# BSPD_RevE.net
KiCad netlist of a schematic drawn in EAGLE
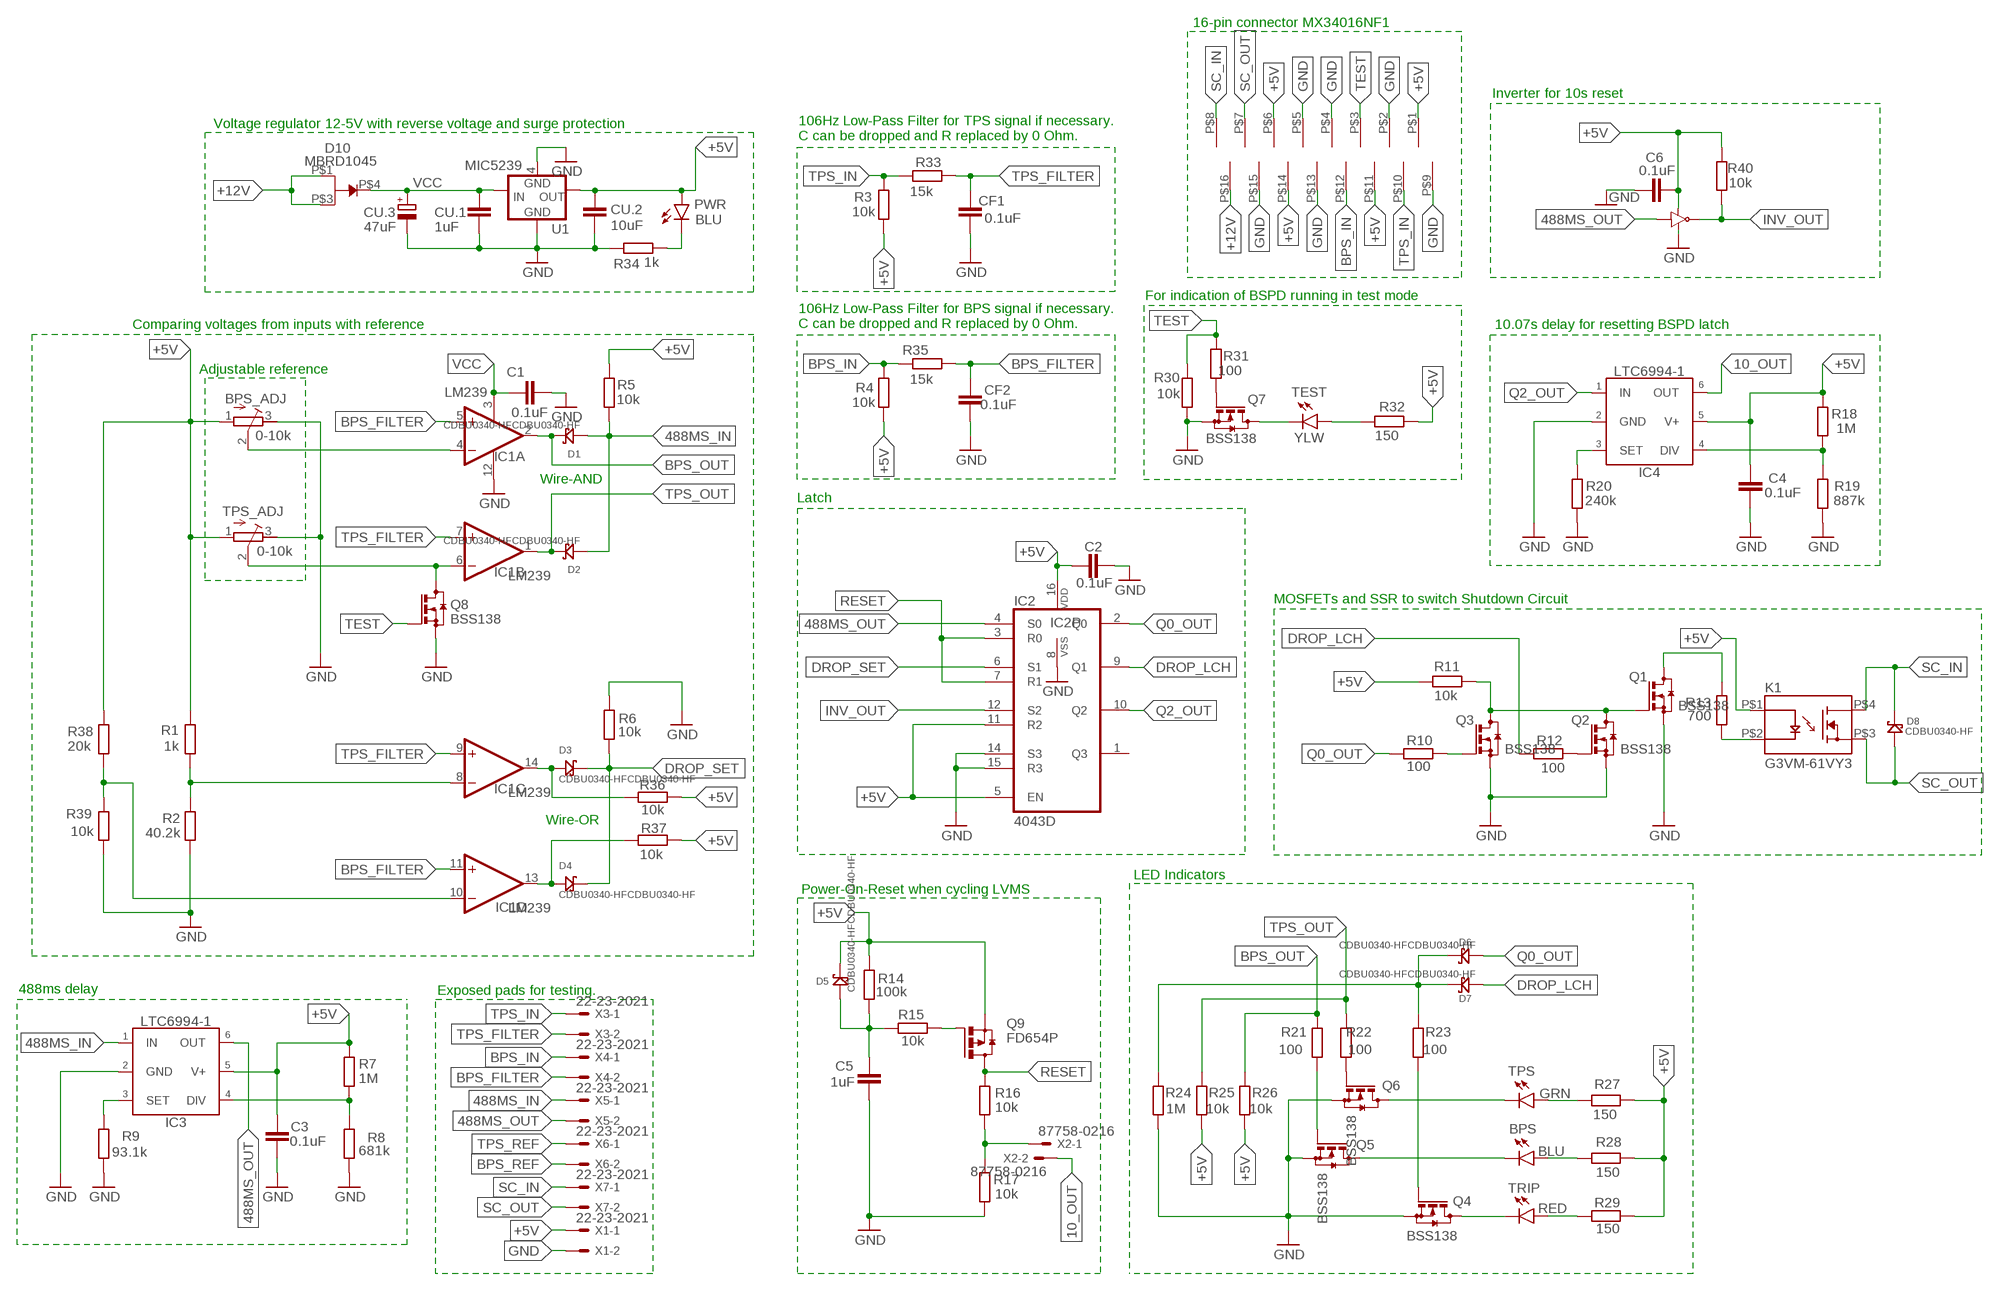
[diagram p0: schematic, sheet 1]

(export (version "E")
  (design (tool "Eeschema 10.0.6"))
  (components
    (comp (ref "BPS")
      (value "BLU")
      (footprint "eagle-import:SML1206")
      (libsource (lib "eagle-import") (part "LEDSML1206"))
    )
    (comp (ref "BPS_ADJ")
      (value "0-10k")
      (footprint "eagle-import:RTRIM3296W")
      (libsource (lib "eagle-import") (part "R-TRIMM3296W"))
    )
    (comp (ref "C1")
      (value "0.1uF")
      (footprint "eagle-import:C0603")
      (libsource (lib "eagle-import") (part "C-EUC0603"))
    )
    (comp (ref "C2")
      (value "0.1uF")
      (footprint "eagle-import:C0603")
      (libsource (lib "eagle-import") (part "C-EUC0603"))
    )
    (comp (ref "C3")
      (value "0.1uF")
      (footprint "eagle-import:C0603")
      (libsource (lib "eagle-import") (part "C-EUC0603"))
    )
    (comp (ref "C4")
      (value "0.1uF")
      (footprint "eagle-import:C0603")
      (libsource (lib "eagle-import") (part "C-EUC0603"))
    )
    (comp (ref "C5")
      (value "1uF")
      (footprint "eagle-import:C0603")
      (libsource (lib "eagle-import") (part "C-EUC0603"))
    )
    (comp (ref "C6")
      (value "0.1uF")
      (footprint "eagle-import:C0603")
      (libsource (lib "eagle-import") (part "C-EUC0603"))
    )
    (comp (ref "CF1")
      (value "0.1uF")
      (footprint "eagle-import:C0603")
      (libsource (lib "eagle-import") (part "C-EUC0603"))
    )
    (comp (ref "CF2")
      (value "0.1uF")
      (footprint "eagle-import:C0603")
      (libsource (lib "eagle-import") (part "C-EUC0603"))
    )
    (comp (ref "CU.1")
      (value "1uF")
      (footprint "eagle-import:C0603")
      (libsource (lib "eagle-import") (part "C-EUC0603"))
    )
    (comp (ref "CU.2")
      (value "10uF")
      (footprint "eagle-import:C0603")
      (libsource (lib "eagle-import") (part "C-EUC0603"))
    )
    (comp (ref "CU.3")
      (value "47uF")
      (footprint "eagle-import:E2-5")
      (libsource (lib "eagle-import") (part "CPOL-EUE2-5"))
    )
    (comp (ref "D1")
      (value "CDBU0340-HFCDBU0340-HF")
      (footprint "eagle-import:DIOM1709X85")
      (libsource (lib "eagle-import") (part "BSPD_CDBU0340-HFCDBU0340-HF"))
    )
    (comp (ref "D2")
      (value "CDBU0340-HFCDBU0340-HF")
      (footprint "eagle-import:DIOM1709X85")
      (libsource (lib "eagle-import") (part "BSPD_CDBU0340-HFCDBU0340-HF"))
    )
    (comp (ref "D3")
      (value "CDBU0340-HFCDBU0340-HF")
      (footprint "eagle-import:DIOM1709X85")
      (libsource (lib "eagle-import") (part "BSPD_CDBU0340-HFCDBU0340-HF"))
    )
    (comp (ref "D4")
      (value "CDBU0340-HFCDBU0340-HF")
      (footprint "eagle-import:DIOM1709X85")
      (libsource (lib "eagle-import") (part "BSPD_CDBU0340-HFCDBU0340-HF"))
    )
    (comp (ref "D5")
      (value "CDBU0340-HFCDBU0340-HF")
      (footprint "eagle-import:DIOM1709X85")
      (libsource (lib "eagle-import") (part "BSPD_CDBU0340-HFCDBU0340-HF"))
    )
    (comp (ref "D6")
      (value "CDBU0340-HFCDBU0340-HF")
      (footprint "eagle-import:DIOM1709X85")
      (libsource (lib "eagle-import") (part "BSPD_CDBU0340-HFCDBU0340-HF"))
    )
    (comp (ref "D7")
      (value "CDBU0340-HFCDBU0340-HF")
      (footprint "eagle-import:DIOM1709X85")
      (libsource (lib "eagle-import") (part "BSPD_CDBU0340-HFCDBU0340-HF"))
    )
    (comp (ref "D8")
      (value "CDBU0340-HF")
      (footprint "eagle-import:DIOM1709X85")
      (libsource (lib "eagle-import") (part "CDBU0340-HFCDBU0340-HF"))
    )
    (comp (ref "D10")
      (value "MBRD1045")
      (footprint "eagle-import:DPAK")
      (libsource (lib "eagle-import") (part "MBRD1045"))
    )
    (comp (ref "IC1")
      (value "LM239")
      (footprint "eagle-import:SO14")
      (libsource (lib "eagle-import") (part "LM2901D"))
    )
    (comp (ref "IC2")
      (value "4043D")
      (footprint "eagle-import:SO16")
      (libsource (lib "eagle-import") (part "4043D"))
    )
    (comp (ref "IC3")
      (value "LTC6994-1")
      (footprint "eagle-import:TSOT23-6")
      (libsource (lib "eagle-import") (part "LTC6994-1"))
    )
    (comp (ref "IC4")
      (value "LTC6994-1")
      (footprint "eagle-import:TSOT23-6")
      (libsource (lib "eagle-import") (part "LTC6994-1"))
    )
    (comp (ref "K1")
      (value "G3VM-61VY3")
      (footprint "eagle-import:SOP-4")
      (libsource (lib "eagle-import") (part "G3VM-61VY3"))
    )
    (comp (ref "P1")
      (value "MX34016NF1")
      (footprint "eagle-import:MX34016NF1")
      (libsource (lib "eagle-import") (part "MX34016NF1"))
    )
    (comp (ref "PWR")
      (value "BLU")
      (footprint "eagle-import:SML1206")
      (libsource (lib "eagle-import") (part "LEDSML1206"))
    )
    (comp (ref "Q1")
      (value "BSS138")
      (footprint "eagle-import:SOT23")
      (libsource (lib "eagle-import") (part "BSS123"))
    )
    (comp (ref "Q2")
      (value "BSS138")
      (footprint "eagle-import:SOT23")
      (libsource (lib "eagle-import") (part "BSS123"))
    )
    (comp (ref "Q3")
      (value "BSS138")
      (footprint "eagle-import:SOT23")
      (libsource (lib "eagle-import") (part "BSS123"))
    )
    (comp (ref "Q4")
      (value "BSS138")
      (footprint "eagle-import:SOT23")
      (libsource (lib "eagle-import") (part "BSS123"))
    )
    (comp (ref "Q5")
      (value "BSS138")
      (footprint "eagle-import:SOT23")
      (libsource (lib "eagle-import") (part "BSS123"))
    )
    (comp (ref "Q6")
      (value "BSS138")
      (footprint "eagle-import:SOT23")
      (libsource (lib "eagle-import") (part "BSS123"))
    )
    (comp (ref "Q7")
      (value "BSS138")
      (footprint "eagle-import:SOT23")
      (libsource (lib "eagle-import") (part "BSS123"))
    )
    (comp (ref "Q8")
      (value "BSS138")
      (footprint "eagle-import:SOT23")
      (libsource (lib "eagle-import") (part "BSS123"))
    )
    (comp (ref "Q9")
      (value "FD654P")
      (footprint "eagle-import:SOT-23-6")
      (libsource (lib "eagle-import") (part "FD654P"))
    )
    (comp (ref "R1")
      (value "1k")
      (footprint "eagle-import:R0603")
      (libsource (lib "eagle-import") (part "R-EU_R0603"))
    )
    (comp (ref "R2")
      (value "40.2k")
      (footprint "eagle-import:R0603")
      (libsource (lib "eagle-import") (part "R-EU_R0603"))
    )
    (comp (ref "R3")
      (value "10k")
      (footprint "eagle-import:R0603")
      (libsource (lib "eagle-import") (part "R-EU_R0603"))
    )
    (comp (ref "R4")
      (value "10k")
      (footprint "eagle-import:R0603")
      (libsource (lib "eagle-import") (part "R-EU_R0603"))
    )
    (comp (ref "R5")
      (value "10k")
      (footprint "eagle-import:R0603")
      (libsource (lib "eagle-import") (part "R-EU_R0603"))
    )
    (comp (ref "R6")
      (value "10k")
      (footprint "eagle-import:R0603")
      (libsource (lib "eagle-import") (part "R-EU_R0603"))
    )
    (comp (ref "R7")
      (value "1M")
      (footprint "eagle-import:R0603")
      (libsource (lib "eagle-import") (part "R-EU_R0603"))
    )
    (comp (ref "R8")
      (value "681k")
      (footprint "eagle-import:R0603")
      (libsource (lib "eagle-import") (part "R-EU_R0603"))
    )
    (comp (ref "R9")
      (value "93.1k")
      (footprint "eagle-import:R0603")
      (libsource (lib "eagle-import") (part "R-EU_R0603"))
    )
    (comp (ref "R10")
      (value "100")
      (footprint "eagle-import:R0603")
      (libsource (lib "eagle-import") (part "R-EU_R0603"))
    )
    (comp (ref "R11")
      (value "10k")
      (footprint "eagle-import:R0603")
      (libsource (lib "eagle-import") (part "R-EU_R0603"))
    )
    (comp (ref "R12")
      (value "100")
      (footprint "eagle-import:R0603")
      (libsource (lib "eagle-import") (part "R-EU_R0603"))
    )
    (comp (ref "R13")
      (value "700")
      (footprint "eagle-import:R0603")
      (libsource (lib "eagle-import") (part "R-EU_R0603"))
    )
    (comp (ref "R14")
      (value "100k")
      (footprint "eagle-import:R0603")
      (libsource (lib "eagle-import") (part "R-EU_R0603"))
    )
    (comp (ref "R15")
      (value "10k")
      (footprint "eagle-import:R0603")
      (libsource (lib "eagle-import") (part "R-EU_R0603"))
    )
    (comp (ref "R16")
      (value "10k")
      (footprint "eagle-import:R0603")
      (libsource (lib "eagle-import") (part "R-EU_R0603"))
    )
    (comp (ref "R17")
      (value "10k")
      (footprint "eagle-import:R0603")
      (libsource (lib "eagle-import") (part "R-EU_R0603"))
    )
    (comp (ref "R18")
      (value "1M")
      (footprint "eagle-import:R0603")
      (libsource (lib "eagle-import") (part "R-EU_R0603"))
    )
    (comp (ref "R19")
      (value "887k")
      (footprint "eagle-import:R0603")
      (libsource (lib "eagle-import") (part "R-EU_R0603"))
    )
    (comp (ref "R20")
      (value "240k")
      (footprint "eagle-import:R0603")
      (libsource (lib "eagle-import") (part "R-EU_R0603"))
    )
    (comp (ref "R21")
      (value "100")
      (footprint "eagle-import:R0603")
      (libsource (lib "eagle-import") (part "R-EU_R0603"))
    )
    (comp (ref "R22")
      (value "100")
      (footprint "eagle-import:R0603")
      (libsource (lib "eagle-import") (part "R-EU_R0603"))
    )
    (comp (ref "R23")
      (value "100")
      (footprint "eagle-import:R0603")
      (libsource (lib "eagle-import") (part "R-EU_R0603"))
    )
    (comp (ref "R24")
      (value "1M")
      (footprint "eagle-import:R0603")
      (libsource (lib "eagle-import") (part "R-EU_R0603"))
    )
    (comp (ref "R25")
      (value "10k")
      (footprint "eagle-import:R0603")
      (libsource (lib "eagle-import") (part "R-EU_R0603"))
    )
    (comp (ref "R26")
      (value "10k")
      (footprint "eagle-import:R0603")
      (libsource (lib "eagle-import") (part "R-EU_R0603"))
    )
    (comp (ref "R27")
      (value "150")
      (footprint "eagle-import:R0603")
      (libsource (lib "eagle-import") (part "R-EU_R0603"))
    )
    (comp (ref "R28")
      (value "150")
      (footprint "eagle-import:R0603")
      (libsource (lib "eagle-import") (part "R-EU_R0603"))
    )
    (comp (ref "R29")
      (value "150")
      (footprint "eagle-import:R0603")
      (libsource (lib "eagle-import") (part "R-EU_R0603"))
    )
    (comp (ref "R30")
      (value "10k")
      (footprint "eagle-import:R0603")
      (libsource (lib "eagle-import") (part "R-EU_R0603"))
    )
    (comp (ref "R31")
      (value "100")
      (footprint "eagle-import:R0603")
      (libsource (lib "eagle-import") (part "R-EU_R0603"))
    )
    (comp (ref "R32")
      (value "150")
      (footprint "eagle-import:R0603")
      (libsource (lib "eagle-import") (part "R-EU_R0603"))
    )
    (comp (ref "R33")
      (value "15k")
      (footprint "eagle-import:R0603")
      (libsource (lib "eagle-import") (part "R-EU_R0603"))
    )
    (comp (ref "R34")
      (value "1k")
      (footprint "eagle-import:R0603")
      (libsource (lib "eagle-import") (part "R-EU_R0603"))
    )
    (comp (ref "R35")
      (value "15k")
      (footprint "eagle-import:R0603")
      (libsource (lib "eagle-import") (part "R-EU_R0603"))
    )
    (comp (ref "R36")
      (value "10k")
      (footprint "eagle-import:R0603")
      (libsource (lib "eagle-import") (part "R-EU_R0603"))
    )
    (comp (ref "R37")
      (value "10k")
      (footprint "eagle-import:R0603")
      (libsource (lib "eagle-import") (part "R-EU_R0603"))
    )
    (comp (ref "R38")
      (value "20k")
      (footprint "eagle-import:R0603")
      (libsource (lib "eagle-import") (part "R-EU_R0603"))
    )
    (comp (ref "R39")
      (value "10k")
      (footprint "eagle-import:R0603")
      (libsource (lib "eagle-import") (part "R-EU_R0603"))
    )
    (comp (ref "R40")
      (value "10k")
      (footprint "eagle-import:R0603")
      (libsource (lib "eagle-import") (part "R-EU_R0603"))
    )
    (comp (ref "TEST")
      (value "YLW")
      (footprint "eagle-import:SML1206")
      (libsource (lib "eagle-import") (part "LEDSML1206"))
    )
    (comp (ref "TPS")
      (value "GRN")
      (footprint "eagle-import:SML1206")
      (libsource (lib "eagle-import") (part "LEDSML1206"))
    )
    (comp (ref "TPS_ADJ")
      (value "0-10k")
      (footprint "eagle-import:RTRIM3296W")
      (libsource (lib "eagle-import") (part "R-TRIMM3296W"))
    )
    (comp (ref "TRIP")
      (value "RED")
      (footprint "eagle-import:SML1206")
      (libsource (lib "eagle-import") (part "LEDSML1206"))
    )
    (comp (ref "U1")
      (value "MIC5239")
      (footprint "eagle-import:SOT223")
      (libsource (lib "eagle-import") (part "MIC5239"))
    )
    (comp (ref "U2")
      (value "74LVC1G06")
      (footprint "eagle-import:SOT353-1")
      (libsource (lib "eagle-import") (part "74LVC1G06"))
    )
    (comp (ref "X1")
      (value "22-23-2021")
      (footprint "eagle-import:22-23-2021")
      (fields (field (name "MF") "MOLEX"))
      (libsource (lib "eagle-import") (part "22-23-2021"))
    )
    (comp (ref "X2")
      (value "87758-0216")
      (footprint "eagle-import:87758-0216")
      (fields (field (name "MF") "MOLEX"))
      (libsource (lib "eagle-import") (part "87758-0216"))
    )
    (comp (ref "X3")
      (value "22-23-2021")
      (footprint "eagle-import:22-23-2021")
      (fields (field (name "MF") "MOLEX"))
      (libsource (lib "eagle-import") (part "22-23-2021"))
    )
    (comp (ref "X4")
      (value "22-23-2021")
      (footprint "eagle-import:22-23-2021")
      (fields (field (name "MF") "MOLEX"))
      (libsource (lib "eagle-import") (part "22-23-2021"))
    )
    (comp (ref "X5")
      (value "22-23-2021")
      (footprint "eagle-import:22-23-2021")
      (fields (field (name "MF") "MOLEX"))
      (libsource (lib "eagle-import") (part "22-23-2021"))
    )
    (comp (ref "X6")
      (value "22-23-2021")
      (footprint "eagle-import:22-23-2021")
      (fields (field (name "MF") "MOLEX"))
      (libsource (lib "eagle-import") (part "22-23-2021"))
    )
    (comp (ref "X7")
      (value "22-23-2021")
      (footprint "eagle-import:22-23-2021")
      (fields (field (name "MF") "MOLEX"))
      (libsource (lib "eagle-import") (part "22-23-2021"))
    )
  )
  (nets
    (net (code "1") (name "+5V") (class "Default")
      (node (ref "BPS_ADJ") (pin "1") (pinfunction "A_1") (pintype "passive"))
      (node (ref "C2") (pin "1") (pinfunction "1_1") (pintype "passive"))
      (node (ref "C3") (pin "2") (pinfunction "2_2") (pintype "passive"))
      (node (ref "C4") (pin "2") (pinfunction "2_2") (pintype "passive"))
      (node (ref "C6") (pin "2") (pinfunction "2_2") (pintype "passive"))
      (node (ref "CU.2") (pin "1") (pinfunction "1_1") (pintype "passive"))
      (node (ref "D5") (pin "1$K") (pinfunction "K_1$K") (pintype "input"))
      (node (ref "IC2") (pin "11") (pinfunction "R2_11") (pintype "input"))
      (node (ref "IC2") (pin "16") (pinfunction "VDD_16") (pintype "power_in"))
      (node (ref "IC2") (pin "5") (pinfunction "EN_5") (pintype "input"))
      (node (ref "IC3") (pin "5") (pinfunction "V+_5") (pintype "passive"))
      (node (ref "IC4") (pin "5") (pinfunction "V+_5") (pintype "passive"))
      (node (ref "K1") (pin "P$1") (pinfunction "2_P$1") (pintype "passive"))
      (node (ref "P1") (pin "P$1") (pinfunction "P$1_P$1") (pintype "input"))
      (node (ref "P1") (pin "P$11") (pinfunction "P$11_P$11") (pintype "input"))
      (node (ref "P1") (pin "P$14") (pinfunction "P$14_P$14") (pintype "input"))
      (node (ref "P1") (pin "P$6") (pinfunction "P$6_P$6") (pintype "input"))
      (node (ref "PWR") (pin "A") (pinfunction "A_A") (pintype "passive"))
      (node (ref "Q9") (pin "4") (pinfunction "S_4") (pintype "passive"))
      (node (ref "R1") (pin "2") (pinfunction "2_2") (pintype "passive"))
      (node (ref "R11") (pin "2") (pinfunction "2_2") (pintype "passive"))
      (node (ref "R14") (pin "2") (pinfunction "2_2") (pintype "passive"))
      (node (ref "R18") (pin "2") (pinfunction "2_2") (pintype "passive"))
      (node (ref "R25") (pin "1") (pinfunction "1_1") (pintype "passive"))
      (node (ref "R26") (pin "1") (pinfunction "1_1") (pintype "passive"))
      (node (ref "R27") (pin "2") (pinfunction "2_2") (pintype "passive"))
      (node (ref "R28") (pin "2") (pinfunction "2_2") (pintype "passive"))
      (node (ref "R29") (pin "2") (pinfunction "2_2") (pintype "passive"))
      (node (ref "R3") (pin "1") (pinfunction "1_1") (pintype "passive"))
      (node (ref "R32") (pin "2") (pinfunction "2_2") (pintype "passive"))
      (node (ref "R36") (pin "1") (pinfunction "1_1") (pintype "passive"))
      (node (ref "R37") (pin "1") (pinfunction "1_1") (pintype "passive"))
      (node (ref "R38") (pin "2") (pinfunction "2_2") (pintype "passive"))
      (node (ref "R4") (pin "1") (pinfunction "1_1") (pintype "passive"))
      (node (ref "R40") (pin "2") (pinfunction "2_2") (pintype "passive"))
      (node (ref "R5") (pin "2") (pinfunction "2_2") (pintype "passive"))
      (node (ref "R7") (pin "2") (pinfunction "2_2") (pintype "passive"))
      (node (ref "TPS_ADJ") (pin "1") (pinfunction "A_1") (pintype "passive"))
      (node (ref "U1") (pin "3") (pinfunction "OUT_3") (pintype "passive"))
      (node (ref "U2") (pin "P$5") (pinfunction "VCC_P$5") (pintype "bidirectional"))
      (node (ref "X1") (pin "1") (pinfunction "S_1") (pintype "passive"))
    )
    (net (code "2") (name "+12V") (class "Default")
      (node (ref "D10") (pin "P$1") (pinfunction "P$1_P$1") (pintype "input"))
      (node (ref "D10") (pin "P$3") (pinfunction "P$3_P$3") (pintype "input"))
      (node (ref "P1") (pin "P$16") (pinfunction "P$16_P$16") (pintype "input"))
    )
    (net (code "3") (name "10_OUT") (class "Default")
      (node (ref "IC4") (pin "6") (pinfunction "OUT_6") (pintype "passive"))
      (node (ref "X2") (pin "2") (pinfunction "S_2") (pintype "passive"))
    )
    (net (code "4") (name "488MS_IN") (class "Default")
      (node (ref "D1") (pin "2$A") (pinfunction "A_2$A") (pintype "input"))
      (node (ref "D2") (pin "2$A") (pinfunction "A_2$A") (pintype "input"))
      (node (ref "IC3") (pin "1") (pinfunction "IN_1") (pintype "passive"))
      (node (ref "R5") (pin "1") (pinfunction "1_1") (pintype "passive"))
      (node (ref "X5") (pin "1") (pinfunction "S_1") (pintype "passive"))
    )
    (net (code "5") (name "488MS_OUT") (class "Default")
      (node (ref "IC2") (pin "4") (pinfunction "S0_4") (pintype "input"))
      (node (ref "IC3") (pin "6") (pinfunction "OUT_6") (pintype "passive"))
      (node (ref "U2") (pin "P$2") (pinfunction "A_P$2") (pintype "input"))
      (node (ref "X5") (pin "2") (pinfunction "S_2") (pintype "passive"))
    )
    (net (code "6") (name "BPS_FILTER") (class "Default")
      (node (ref "CF2") (pin "2") (pinfunction "2_2") (pintype "passive"))
      (node (ref "IC1") (pin "11") (pinfunction "+IN_11") (pintype "input"))
      (node (ref "IC1") (pin "5") (pinfunction "+IN_5") (pintype "input"))
      (node (ref "R35") (pin "1") (pinfunction "1_1") (pintype "passive"))
      (node (ref "X4") (pin "2") (pinfunction "S_2") (pintype "passive"))
    )
    (net (code "7") (name "BPS_IN") (class "Default")
      (node (ref "P1") (pin "P$12") (pinfunction "P$12_P$12") (pintype "input"))
      (node (ref "R35") (pin "2") (pinfunction "2_2") (pintype "passive"))
      (node (ref "R4") (pin "2") (pinfunction "2_2") (pintype "passive"))
      (node (ref "X4") (pin "1") (pinfunction "S_1") (pintype "passive"))
    )
    (net (code "8") (name "BPS_OUT") (class "Default")
      (node (ref "D1") (pin "1$K") (pinfunction "K_1$K") (pintype "input"))
      (node (ref "IC1") (pin "2") (pinfunction "OUT_2") (pintype "output"))
      (node (ref "R21") (pin "2") (pinfunction "2_2") (pintype "passive"))
      (node (ref "R26") (pin "2") (pinfunction "2_2") (pintype "passive"))
    )
    (net (code "9") (name "BPS_REF") (class "Default")
      (node (ref "BPS_ADJ") (pin "2") (pinfunction "S_2") (pintype "passive"))
      (node (ref "IC1") (pin "4") (pinfunction "-IN_4") (pintype "input"))
      (node (ref "X6") (pin "2") (pinfunction "S_2") (pintype "passive"))
    )
    (net (code "10") (name "DROP_LCH") (class "Default")
      (node (ref "D7") (pin "2$A") (pinfunction "A_2$A") (pintype "input"))
      (node (ref "IC2") (pin "9") (pinfunction "Q1_9") (pintype "output"))
      (node (ref "R12") (pin "2") (pinfunction "2_2") (pintype "passive"))
    )
    (net (code "11") (name "DROP_SET") (class "Default")
      (node (ref "D3") (pin "1$K") (pinfunction "K_1$K") (pintype "input"))
      (node (ref "D4") (pin "1$K") (pinfunction "K_1$K") (pintype "input"))
      (node (ref "IC2") (pin "6") (pinfunction "S1_6") (pintype "input"))
      (node (ref "R6") (pin "1") (pinfunction "1_1") (pintype "passive"))
    )
    (net (code "12") (name "GND") (class "Default")
      (node (ref "BPS_ADJ") (pin "3") (pinfunction "E_3") (pintype "passive"))
      (node (ref "C1") (pin "2") (pinfunction "2_2") (pintype "passive"))
      (node (ref "C2") (pin "2") (pinfunction "2_2") (pintype "passive"))
      (node (ref "C3") (pin "1") (pinfunction "1_1") (pintype "passive"))
      (node (ref "C4") (pin "1") (pinfunction "1_1") (pintype "passive"))
      (node (ref "C5") (pin "1") (pinfunction "1_1") (pintype "passive"))
      (node (ref "C6") (pin "1") (pinfunction "1_1") (pintype "passive"))
      (node (ref "CF1") (pin "1") (pinfunction "1_1") (pintype "passive"))
      (node (ref "CF2") (pin "1") (pinfunction "1_1") (pintype "passive"))
      (node (ref "CU.1") (pin "2") (pinfunction "2_2") (pintype "passive"))
      (node (ref "CU.2") (pin "2") (pinfunction "2_2") (pintype "passive"))
      (node (ref "CU.3") (pin "-") (pinfunction "-_-") (pintype "passive"))
      (node (ref "IC1") (pin "12") (pinfunction "V-_12") (pintype "power_in"))
      (node (ref "IC2") (pin "14") (pinfunction "S3_14") (pintype "input"))
      (node (ref "IC2") (pin "15") (pinfunction "R3_15") (pintype "input"))
      (node (ref "IC2") (pin "8") (pinfunction "VSS_8") (pintype "power_in"))
      (node (ref "IC3") (pin "2") (pinfunction "GND_2") (pintype "passive"))
      (node (ref "IC4") (pin "2") (pinfunction "GND_2") (pintype "passive"))
      (node (ref "P1") (pin "P$13") (pinfunction "P$13_P$13") (pintype "input"))
      (node (ref "P1") (pin "P$15") (pinfunction "P$15_P$15") (pintype "input"))
      (node (ref "P1") (pin "P$2") (pinfunction "P$2_P$2") (pintype "input"))
      (node (ref "P1") (pin "P$4") (pinfunction "P$4_P$4") (pintype "input"))
      (node (ref "P1") (pin "P$5") (pinfunction "P$5_P$5") (pintype "input"))
      (node (ref "P1") (pin "P$9") (pinfunction "P$9_P$9") (pintype "input"))
      (node (ref "Q1") (pin "2") (pinfunction "S_2") (pintype "passive"))
      (node (ref "Q2") (pin "2") (pinfunction "S_2") (pintype "passive"))
      (node (ref "Q3") (pin "2") (pinfunction "S_2") (pintype "passive"))
      (node (ref "Q4") (pin "2") (pinfunction "S_2") (pintype "passive"))
      (node (ref "Q5") (pin "2") (pinfunction "S_2") (pintype "passive"))
      (node (ref "Q6") (pin "2") (pinfunction "S_2") (pintype "passive"))
      (node (ref "Q7") (pin "2") (pinfunction "S_2") (pintype "passive"))
      (node (ref "Q8") (pin "2") (pinfunction "S_2") (pintype "passive"))
      (node (ref "R17") (pin "2") (pinfunction "2_2") (pintype "passive"))
      (node (ref "R19") (pin "1") (pinfunction "1_1") (pintype "passive"))
      (node (ref "R2") (pin "1") (pinfunction "1_1") (pintype "passive"))
      (node (ref "R20") (pin "1") (pinfunction "1_1") (pintype "passive"))
      (node (ref "R24") (pin "1") (pinfunction "1_1") (pintype "passive"))
      (node (ref "R30") (pin "1") (pinfunction "1_1") (pintype "passive"))
      (node (ref "R34") (pin "1") (pinfunction "1_1") (pintype "passive"))
      (node (ref "R39") (pin "1") (pinfunction "1_1") (pintype "passive"))
      (node (ref "R6") (pin "2") (pinfunction "2_2") (pintype "passive"))
      (node (ref "R8") (pin "1") (pinfunction "1_1") (pintype "passive"))
      (node (ref "R9") (pin "1") (pinfunction "1_1") (pintype "passive"))
      (node (ref "TPS_ADJ") (pin "3") (pinfunction "E_3") (pintype "passive"))
      (node (ref "U1") (pin "2") (pinfunction "GND_2") (pintype "input"))
      (node (ref "U1") (pin "4") (pinfunction "GND_TAB_4") (pintype "input"))
      (node (ref "U2") (pin "P$3") (pinfunction "GND_P$3") (pintype "bidirectional"))
      (node (ref "X1") (pin "2") (pinfunction "S_2") (pintype "passive"))
    )
    (net (code "13") (name "INV_OUT") (class "Default")
      (node (ref "IC2") (pin "12") (pinfunction "S2_12") (pintype "input"))
      (node (ref "R40") (pin "1") (pinfunction "1_1") (pintype "passive"))
      (node (ref "U2") (pin "P$4") (pinfunction "Y_P$4") (pintype "output"))
    )
    (net (code "14") (name "Net-(BPS-PadA)") (class "Default")
      (node (ref "BPS") (pin "A") (pinfunction "A_A") (pintype "passive"))
      (node (ref "R28") (pin "1") (pinfunction "1_1") (pintype "passive"))
    )
    (net (code "15") (name "Net-(D3-A)") (class "Default")
      (node (ref "D3") (pin "2$A") (pinfunction "A_2$A") (pintype "input"))
      (node (ref "IC1") (pin "14") (pinfunction "OUT_14") (pintype "output"))
      (node (ref "R36") (pin "2") (pinfunction "2_2") (pintype "passive"))
    )
    (net (code "16") (name "Net-(D4-A)") (class "Default")
      (node (ref "D4") (pin "2$A") (pinfunction "A_2$A") (pintype "input"))
      (node (ref "IC1") (pin "13") (pinfunction "OUT_13") (pintype "output"))
      (node (ref "R37") (pin "2") (pinfunction "2_2") (pintype "passive"))
    )
    (net (code "17") (name "Net-(D5-A)") (class "Default")
      (node (ref "C5") (pin "2") (pinfunction "2_2") (pintype "passive"))
      (node (ref "D5") (pin "2$A") (pinfunction "A_2$A") (pintype "input"))
      (node (ref "R14") (pin "1") (pinfunction "1_1") (pintype "passive"))
      (node (ref "R15") (pin "2") (pinfunction "2_2") (pintype "passive"))
    )
    (net (code "18") (name "Net-(D6-K)") (class "Default")
      (node (ref "D6") (pin "1$K") (pinfunction "K_1$K") (pintype "input"))
      (node (ref "D7") (pin "1$K") (pinfunction "K_1$K") (pintype "input"))
      (node (ref "R23") (pin "2") (pinfunction "2_2") (pintype "passive"))
      (node (ref "R24") (pin "2") (pinfunction "2_2") (pintype "passive"))
    )
    (net (code "19") (name "Net-(IC1C--IN)") (class "Default")
      (node (ref "IC1") (pin "8") (pinfunction "-IN_8") (pintype "input"))
      (node (ref "R1") (pin "1") (pinfunction "1_1") (pintype "passive"))
      (node (ref "R2") (pin "2") (pinfunction "2_2") (pintype "passive"))
    )
    (net (code "20") (name "Net-(IC1D--IN)") (class "Default")
      (node (ref "IC1") (pin "10") (pinfunction "-IN_10") (pintype "input"))
      (node (ref "R38") (pin "1") (pinfunction "1_1") (pintype "passive"))
      (node (ref "R39") (pin "2") (pinfunction "2_2") (pintype "passive"))
    )
    (net (code "21") (name "Net-(IC3-DIV)") (class "Default")
      (node (ref "IC3") (pin "4") (pinfunction "DIV_4") (pintype "passive"))
      (node (ref "R7") (pin "1") (pinfunction "1_1") (pintype "passive"))
      (node (ref "R8") (pin "2") (pinfunction "2_2") (pintype "passive"))
    )
    (net (code "22") (name "Net-(IC3-SET)") (class "Default")
      (node (ref "IC3") (pin "3") (pinfunction "SET_3") (pintype "passive"))
      (node (ref "R9") (pin "2") (pinfunction "2_2") (pintype "passive"))
    )
    (net (code "23") (name "Net-(IC4-DIV)") (class "Default")
      (node (ref "IC4") (pin "4") (pinfunction "DIV_4") (pintype "passive"))
      (node (ref "R18") (pin "1") (pinfunction "1_1") (pintype "passive"))
      (node (ref "R19") (pin "2") (pinfunction "2_2") (pintype "passive"))
    )
    (net (code "24") (name "Net-(IC4-SET)") (class "Default")
      (node (ref "IC4") (pin "3") (pinfunction "SET_3") (pintype "passive"))
      (node (ref "R20") (pin "2") (pinfunction "2_2") (pintype "passive"))
    )
    (net (code "25") (name "Net-(K1-1)") (class "Default")
      (node (ref "K1") (pin "P$2") (pinfunction "1_P$2") (pintype "passive"))
      (node (ref "R13") (pin "1") (pinfunction "1_1") (pintype "passive"))
    )
    (net (code "26") (name "Net-(PWR-PadC)") (class "Default")
      (node (ref "PWR") (pin "C") (pinfunction "C_C") (pintype "passive"))
      (node (ref "R34") (pin "2") (pinfunction "2_2") (pintype "passive"))
    )
    (net (code "27") (name "Net-(Q1-D)") (class "Default")
      (node (ref "Q1") (pin "3") (pinfunction "D_3") (pintype "passive"))
      (node (ref "R13") (pin "2") (pinfunction "2_2") (pintype "passive"))
    )
    (net (code "28") (name "Net-(Q1-G)") (class "Default")
      (node (ref "Q1") (pin "1") (pinfunction "G_1") (pintype "passive"))
      (node (ref "Q2") (pin "3") (pinfunction "D_3") (pintype "passive"))
      (node (ref "Q3") (pin "3") (pinfunction "D_3") (pintype "passive"))
      (node (ref "R11") (pin "1") (pinfunction "1_1") (pintype "passive"))
    )
    (net (code "29") (name "Net-(Q2-G)") (class "Default")
      (node (ref "Q2") (pin "1") (pinfunction "G_1") (pintype "passive"))
      (node (ref "R12") (pin "1") (pinfunction "1_1") (pintype "passive"))
    )
    (net (code "30") (name "Net-(Q3-G)") (class "Default")
      (node (ref "Q3") (pin "1") (pinfunction "G_1") (pintype "passive"))
      (node (ref "R10") (pin "2") (pinfunction "2_2") (pintype "passive"))
    )
    (net (code "31") (name "Net-(Q4-D)") (class "Default")
      (node (ref "Q4") (pin "3") (pinfunction "D_3") (pintype "passive"))
      (node (ref "TRIP") (pin "C") (pinfunction "C_C") (pintype "passive"))
    )
    (net (code "32") (name "Net-(Q4-G)") (class "Default")
      (node (ref "Q4") (pin "1") (pinfunction "G_1") (pintype "passive"))
      (node (ref "R23") (pin "1") (pinfunction "1_1") (pintype "passive"))
    )
    (net (code "33") (name "Net-(Q5-D)") (class "Default")
      (node (ref "BPS") (pin "C") (pinfunction "C_C") (pintype "passive"))
      (node (ref "Q5") (pin "3") (pinfunction "D_3") (pintype "passive"))
    )
    (net (code "34") (name "Net-(Q5-G)") (class "Default")
      (node (ref "Q5") (pin "1") (pinfunction "G_1") (pintype "passive"))
      (node (ref "R21") (pin "1") (pinfunction "1_1") (pintype "passive"))
    )
    (net (code "35") (name "Net-(Q6-D)") (class "Default")
      (node (ref "Q6") (pin "3") (pinfunction "D_3") (pintype "passive"))
      (node (ref "TPS") (pin "C") (pinfunction "C_C") (pintype "passive"))
    )
    (net (code "36") (name "Net-(Q6-G)") (class "Default")
      (node (ref "Q6") (pin "1") (pinfunction "G_1") (pintype "passive"))
      (node (ref "R22") (pin "1") (pinfunction "1_1") (pintype "passive"))
    )
    (net (code "37") (name "Net-(Q7-D)") (class "Default")
      (node (ref "Q7") (pin "3") (pinfunction "D_3") (pintype "passive"))
      (node (ref "TEST") (pin "C") (pinfunction "C_C") (pintype "passive"))
    )
    (net (code "38") (name "Net-(Q7-G)") (class "Default")
      (node (ref "Q7") (pin "1") (pinfunction "G_1") (pintype "passive"))
      (node (ref "R31") (pin "1") (pinfunction "1_1") (pintype "passive"))
    )
    (net (code "39") (name "Net-(Q9-G)") (class "Default")
      (node (ref "Q9") (pin "3") (pinfunction "G_3") (pintype "passive"))
      (node (ref "R15") (pin "1") (pinfunction "1_1") (pintype "passive"))
    )
    (net (code "40") (name "Net-(R27-Pad1)") (class "Default")
      (node (ref "R27") (pin "1") (pinfunction "1_1") (pintype "passive"))
      (node (ref "TPS") (pin "A") (pinfunction "A_A") (pintype "passive"))
    )
    (net (code "41") (name "Net-(R29-Pad1)") (class "Default")
      (node (ref "R29") (pin "1") (pinfunction "1_1") (pintype "passive"))
      (node (ref "TRIP") (pin "A") (pinfunction "A_A") (pintype "passive"))
    )
    (net (code "42") (name "Net-(R32-Pad1)") (class "Default")
      (node (ref "R32") (pin "1") (pinfunction "1_1") (pintype "passive"))
      (node (ref "TEST") (pin "A") (pinfunction "A_A") (pintype "passive"))
    )
    (net (code "43") (name "Net-(X2A-S)") (class "Default")
      (node (ref "R16") (pin "2") (pinfunction "2_2") (pintype "passive"))
      (node (ref "R17") (pin "1") (pinfunction "1_1") (pintype "passive"))
      (node (ref "X2") (pin "1") (pinfunction "S_1") (pintype "passive"))
    )
    (net (code "44") (name "Q0_OUT") (class "Default")
      (node (ref "D6") (pin "2$A") (pinfunction "A_2$A") (pintype "input"))
      (node (ref "IC2") (pin "2") (pinfunction "Q0_2") (pintype "output"))
      (node (ref "R10") (pin "1") (pinfunction "1_1") (pintype "passive"))
    )
    (net (code "45") (name "Q2_OUT") (class "Default")
      (node (ref "IC2") (pin "10") (pinfunction "Q2_10") (pintype "output"))
      (node (ref "IC4") (pin "1") (pinfunction "IN_1") (pintype "passive"))
    )
    (net (code "46") (name "RESET") (class "Default")
      (node (ref "IC2") (pin "3") (pinfunction "R0_3") (pintype "input"))
      (node (ref "IC2") (pin "7") (pinfunction "R1_7") (pintype "input"))
      (node (ref "Q9") (pin "1") (pinfunction "D_1") (pintype "passive"))
      (node (ref "Q9") (pin "2") (pinfunction "D_2") (pintype "passive"))
      (node (ref "Q9") (pin "5") (pinfunction "D_5") (pintype "passive"))
      (node (ref "Q9") (pin "6") (pinfunction "D_6") (pintype "passive"))
      (node (ref "R16") (pin "1") (pinfunction "1_1") (pintype "passive"))
    )
    (net (code "47") (name "SC_IN") (class "Default")
      (node (ref "D8") (pin "1$K") (pinfunction "K_1$K") (pintype "input"))
      (node (ref "K1") (pin "P$4") (pinfunction "4_P$4") (pintype "passive"))
      (node (ref "P1") (pin "P$8") (pinfunction "P$8_P$8") (pintype "input"))
      (node (ref "X7") (pin "1") (pinfunction "S_1") (pintype "passive"))
    )
    (net (code "48") (name "SC_OUT") (class "Default")
      (node (ref "D8") (pin "2$A") (pinfunction "A_2$A") (pintype "input"))
      (node (ref "K1") (pin "P$3") (pinfunction "3_P$3") (pintype "passive"))
      (node (ref "P1") (pin "P$7") (pinfunction "P$7_P$7") (pintype "input"))
      (node (ref "X7") (pin "2") (pinfunction "S_2") (pintype "passive"))
    )
    (net (code "49") (name "TEST") (class "Default")
      (node (ref "P1") (pin "P$3") (pinfunction "P$3_P$3") (pintype "input"))
      (node (ref "Q8") (pin "1") (pinfunction "G_1") (pintype "passive"))
      (node (ref "R30") (pin "2") (pinfunction "2_2") (pintype "passive"))
      (node (ref "R31") (pin "2") (pinfunction "2_2") (pintype "passive"))
    )
    (net (code "50") (name "TPS_FILTER") (class "Default")
      (node (ref "CF1") (pin "2") (pinfunction "2_2") (pintype "passive"))
      (node (ref "IC1") (pin "7") (pinfunction "+IN_7") (pintype "input"))
      (node (ref "IC1") (pin "9") (pinfunction "+IN_9") (pintype "input"))
      (node (ref "R33") (pin "1") (pinfunction "1_1") (pintype "passive"))
      (node (ref "X3") (pin "2") (pinfunction "S_2") (pintype "passive"))
    )
    (net (code "51") (name "TPS_IN") (class "Default")
      (node (ref "P1") (pin "P$10") (pinfunction "P$10_P$10") (pintype "input"))
      (node (ref "R3") (pin "2") (pinfunction "2_2") (pintype "passive"))
      (node (ref "R33") (pin "2") (pinfunction "2_2") (pintype "passive"))
      (node (ref "X3") (pin "1") (pinfunction "S_1") (pintype "passive"))
    )
    (net (code "52") (name "TPS_OUT") (class "Default")
      (node (ref "D2") (pin "1$K") (pinfunction "K_1$K") (pintype "input"))
      (node (ref "IC1") (pin "1") (pinfunction "OUT_1") (pintype "output"))
      (node (ref "R22") (pin "2") (pinfunction "2_2") (pintype "passive"))
      (node (ref "R25") (pin "2") (pinfunction "2_2") (pintype "passive"))
    )
    (net (code "53") (name "TPS_REF") (class "Default")
      (node (ref "IC1") (pin "6") (pinfunction "-IN_6") (pintype "input"))
      (node (ref "Q8") (pin "3") (pinfunction "D_3") (pintype "passive"))
      (node (ref "TPS_ADJ") (pin "2") (pinfunction "S_2") (pintype "passive"))
      (node (ref "X6") (pin "1") (pinfunction "S_1") (pintype "passive"))
    )
    (net (code "54") (name "VCC") (class "Default")
      (node (ref "C1") (pin "1") (pinfunction "1_1") (pintype "passive"))
      (node (ref "CU.1") (pin "1") (pinfunction "1_1") (pintype "passive"))
      (node (ref "CU.3") (pin "+") (pinfunction "+_+") (pintype "passive"))
      (node (ref "D10") (pin "P$4") (pinfunction "P$4_P$4") (pintype "output"))
      (node (ref "IC1") (pin "3") (pinfunction "V+_3") (pintype "power_in"))
      (node (ref "U1") (pin "1") (pinfunction "IN_1") (pintype "input"))
    )
    (net (code "55") (name "unconnected-(IC2A-Q3-Pad1)") (class "Default")
      (node (ref "IC2") (pin "1") (pinfunction "Q3_1") (pintype "output"))
    )
  )
)
